# rapidshark-main-breakout-bottom-mk-1_0.net
KiCad netlist of a schematic drawn in EAGLE
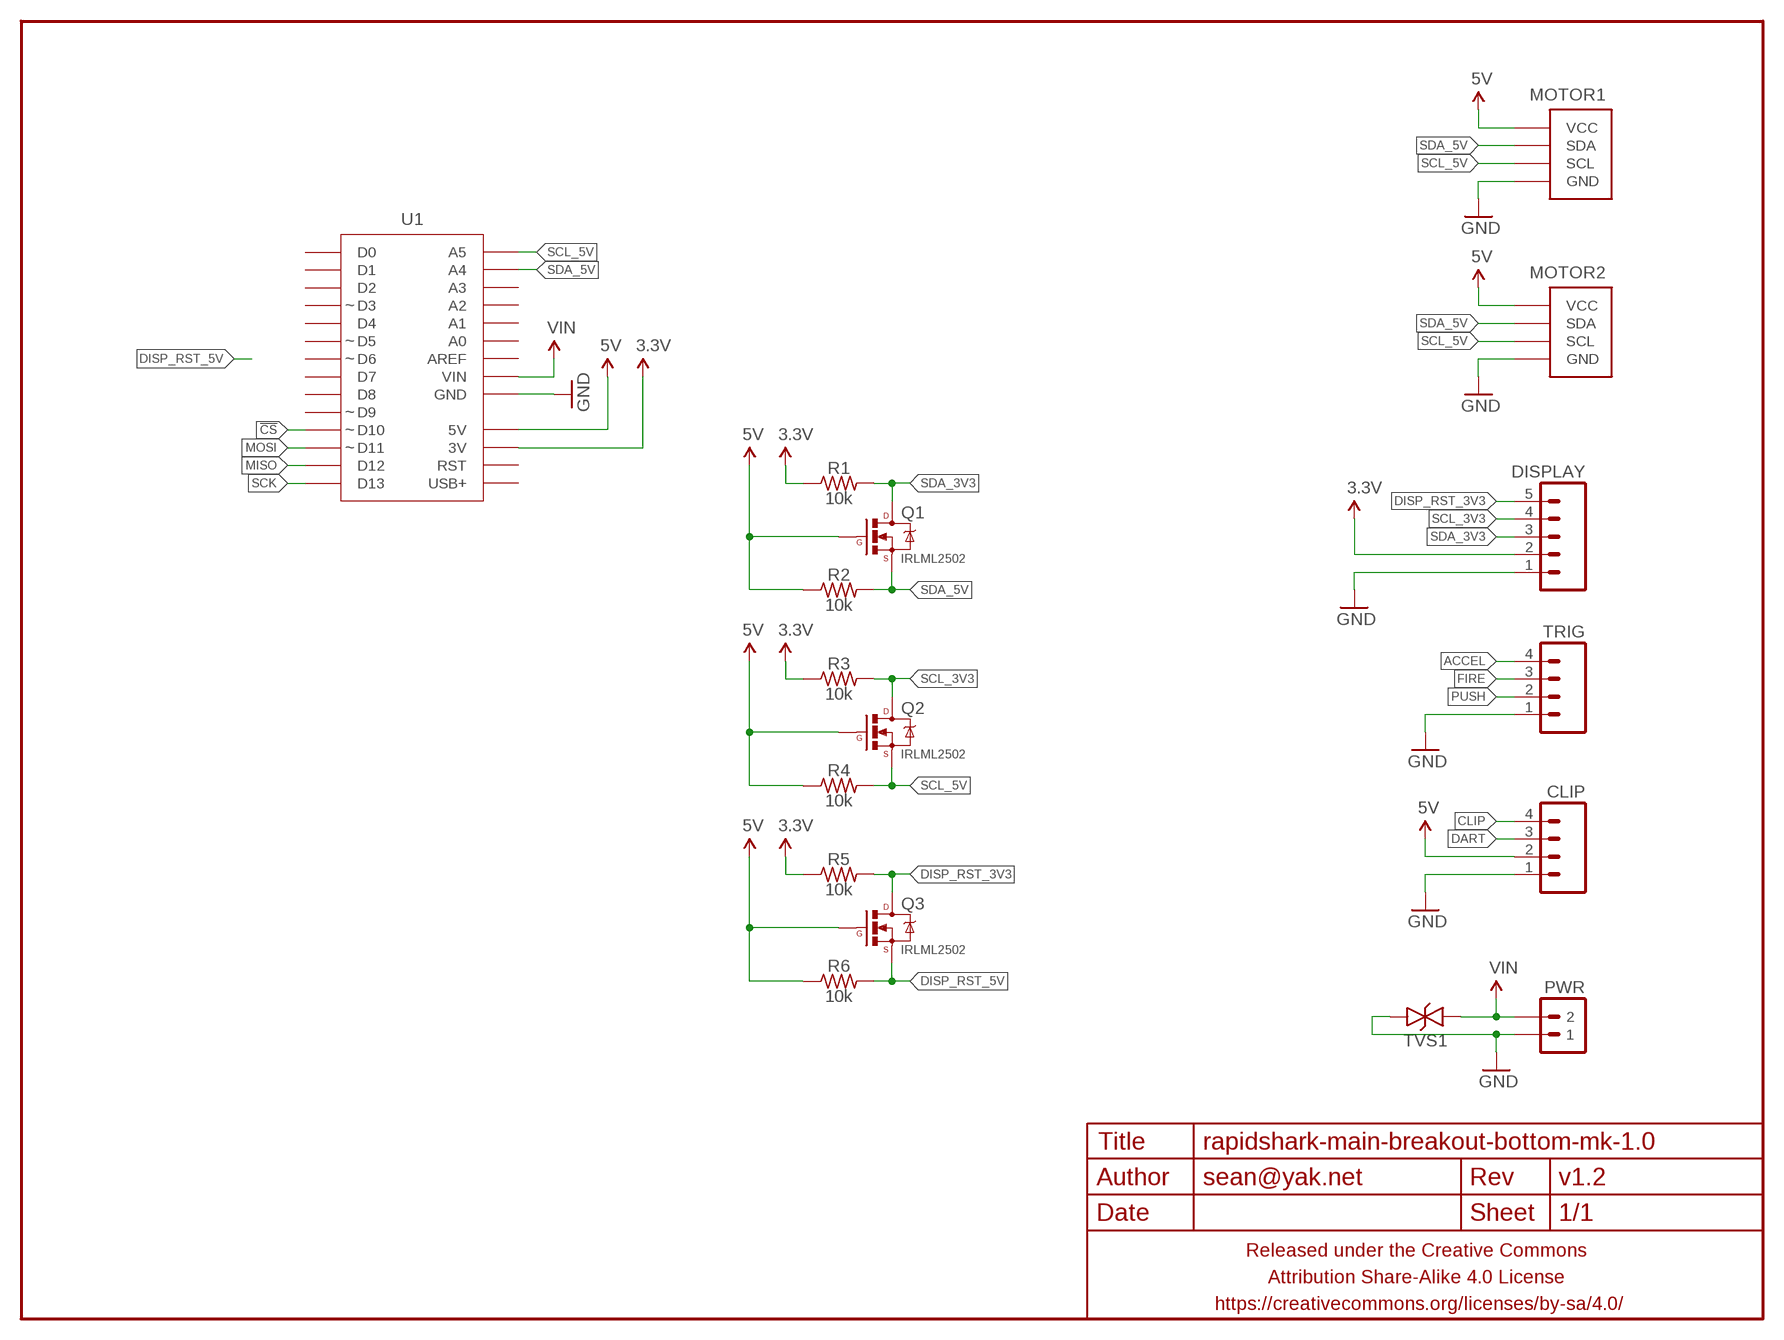
[diagram p0: schematic, sheet 1]

(export (version "E")
  (design (tool "Eeschema 10.0.6"))
  (components
    (comp (ref "CLIP")
      (value "M04JST-PTH-VERT")
      (footprint "eagle-import:JST-4-PH-VERT-PTH")
      (libsource (lib "eagle-import") (part "M04JST-PTH-VERT"))
    )
    (comp (ref "DISPLAY")
      (value "M05JST-PH-VERT-PTH")
      (footprint "eagle-import:JST-5-PH-VERT-PTH")
      (libsource (lib "eagle-import") (part "M05JST-PH-VERT-PTH"))
    )
    (comp (ref "FRAME1")
      (value "FRAME-LETTERNO_PACKAGE")
      (footprint "eagle-import:DUMMY")
      (fields (field (name "DESIGNER") "sean@yak.net") (field (name "VERSION") "v1.2"))
      (libsource (lib "eagle-import") (part "FRAME-LETTERNO_PACKAGE"))
    )
    (comp (ref "MOTOR1")
      (value "M04-I2CJST-4-PH-VERT-NS")
      (footprint "eagle-import:JST-4-PH-VERT-PTH")
      (libsource (lib "eagle-import") (part "M04-I2CJST-4-PH-VERT-NS"))
    )
    (comp (ref "MOTOR2")
      (value "M04-I2CJST-4-PH-VERT-NS")
      (footprint "eagle-import:JST-4-PH-VERT-PTH")
      (libsource (lib "eagle-import") (part "M04-I2CJST-4-PH-VERT-NS"))
    )
    (comp (ref "PWR")
      (value "M02PTH-CENTERED-R+")
      (footprint "eagle-import:1X02-CENTER-R+")
      (libsource (lib "eagle-import") (part "M02PTH-CENTERED-R+"))
    )
    (comp (ref "Q1")
      (value "IRLML2502")
      (footprint "eagle-import:SOT23")
      (libsource (lib "eagle-import") (part "MOSFET-NCHANNELIRLML2502"))
    )
    (comp (ref "Q2")
      (value "IRLML2502")
      (footprint "eagle-import:SOT23")
      (libsource (lib "eagle-import") (part "MOSFET-NCHANNELIRLML2502"))
    )
    (comp (ref "Q3")
      (value "IRLML2502")
      (footprint "eagle-import:SOT23")
      (libsource (lib "eagle-import") (part "MOSFET-NCHANNELIRLML2502"))
    )
    (comp (ref "R1")
      (value "10k")
      (footprint "eagle-import:R0603")
      (libsource (lib "eagle-import") (part "RESISTORR0603"))
    )
    (comp (ref "R2")
      (value "10k")
      (footprint "eagle-import:R0603")
      (libsource (lib "eagle-import") (part "RESISTORR0603"))
    )
    (comp (ref "R3")
      (value "10k")
      (footprint "eagle-import:R0603")
      (libsource (lib "eagle-import") (part "RESISTORR0603"))
    )
    (comp (ref "R4")
      (value "10k")
      (footprint "eagle-import:R0603")
      (libsource (lib "eagle-import") (part "RESISTORR0603"))
    )
    (comp (ref "R5")
      (value "10k")
      (footprint "eagle-import:R0603")
      (libsource (lib "eagle-import") (part "RESISTORR0603"))
    )
    (comp (ref "R6")
      (value "10k")
      (footprint "eagle-import:R0603")
      (libsource (lib "eagle-import") (part "RESISTORR0603"))
    )
    (comp (ref "TRIG")
      (value "M04JST-PTH-VERT")
      (footprint "eagle-import:JST-4-PH-VERT-PTH")
      (libsource (lib "eagle-import") (part "M04JST-PTH-VERT"))
    )
    (comp (ref "TVS1")
      (value "TVSSMA")
      (footprint "eagle-import:SMA-DIODE-TVS-BIDIR")
      (libsource (lib "eagle-import") (part "TVSSMA"))
    )
    (comp (ref "U1")
      (value "ADAFRUIT_METRO_MININOHOLES-OUTSIDER")
      (footprint "eagle-import:ADAFRUIT_METRO_MINI_OUTSIDER")
      (libsource (lib "eagle-import") (part "ADAFRUIT_METRO_MININOHOLES-OUTSIDER"))
    )
  )
  (nets
    (net (code "1") (name "/~{CS}") (class "Default")
      (node (ref "U1") (pin "11") (pinfunction "D10_11") (pintype "bidirectional"))
    )
    (net (code "2") (name "3.3V") (class "Default")
      (node (ref "DISPLAY") (pin "2") (pinfunction "2_2") (pintype "passive"))
      (node (ref "R1") (pin "1") (pinfunction "1_1") (pintype "passive"))
      (node (ref "R3") (pin "1") (pinfunction "1_1") (pintype "passive"))
      (node (ref "R5") (pin "1") (pinfunction "1_1") (pintype "passive"))
      (node (ref "U1") (pin "17") (pinfunction "3V_17") (pintype "bidirectional"))
    )
    (net (code "3") (name "5V") (class "Default")
      (node (ref "CLIP") (pin "2") (pinfunction "2_2") (pintype "passive"))
      (node (ref "MOTOR1") (pin "2") (pinfunction "VCC_2") (pintype "bidirectional"))
      (node (ref "MOTOR2") (pin "2") (pinfunction "VCC_2") (pintype "bidirectional"))
      (node (ref "Q1") (pin "1") (pinfunction "G_1") (pintype "passive"))
      (node (ref "Q2") (pin "1") (pinfunction "G_1") (pintype "passive"))
      (node (ref "Q3") (pin "1") (pinfunction "G_1") (pintype "passive"))
      (node (ref "R2") (pin "1") (pinfunction "1_1") (pintype "passive"))
      (node (ref "R4") (pin "1") (pinfunction "1_1") (pintype "passive"))
      (node (ref "R6") (pin "1") (pinfunction "1_1") (pintype "passive"))
      (node (ref "U1") (pin "18") (pinfunction "5V_18") (pintype "bidirectional"))
    )
    (net (code "4") (name "ACCEL") (class "Default")
      (node (ref "TRIG") (pin "4") (pinfunction "4_4") (pintype "passive"))
    )
    (net (code "5") (name "CLIP") (class "Default")
      (node (ref "CLIP") (pin "4") (pinfunction "4_4") (pintype "passive"))
    )
    (net (code "6") (name "DART") (class "Default")
      (node (ref "CLIP") (pin "3") (pinfunction "3_3") (pintype "passive"))
    )
    (net (code "7") (name "DISP_RST_3V3") (class "Default")
      (node (ref "DISPLAY") (pin "5") (pinfunction "5_5") (pintype "passive"))
      (node (ref "Q3") (pin "3") (pinfunction "D_3") (pintype "passive"))
      (node (ref "R5") (pin "2") (pinfunction "2_2") (pintype "passive"))
    )
    (net (code "8") (name "DISP_RST_5V") (class "Default")
      (node (ref "Q3") (pin "2") (pinfunction "S_2") (pintype "passive"))
      (node (ref "R6") (pin "2") (pinfunction "2_2") (pintype "passive"))
    )
    (net (code "9") (name "FIRE") (class "Default")
      (node (ref "TRIG") (pin "3") (pinfunction "3_3") (pintype "passive"))
    )
    (net (code "10") (name "GND") (class "Default")
      (node (ref "CLIP") (pin "1") (pinfunction "1_1") (pintype "passive"))
      (node (ref "DISPLAY") (pin "1") (pinfunction "1_1") (pintype "passive"))
      (node (ref "MOTOR1") (pin "1") (pinfunction "GND_1") (pintype "bidirectional"))
      (node (ref "MOTOR2") (pin "1") (pinfunction "GND_1") (pintype "bidirectional"))
      (node (ref "PWR") (pin "1") (pinfunction "1_1") (pintype "passive"))
      (node (ref "TRIG") (pin "1") (pinfunction "1_1") (pintype "passive"))
      (node (ref "TVS1") (pin "2") (pinfunction "2_2") (pintype "passive"))
      (node (ref "U1") (pin "19") (pinfunction "GND_19") (pintype "bidirectional"))
      (node (ref "U1") (pin "20") (pinfunction "GND_20") (pintype "bidirectional"))
    )
    (net (code "11") (name "MISO") (class "Default")
      (node (ref "U1") (pin "13") (pinfunction "D12_13") (pintype "bidirectional"))
    )
    (net (code "12") (name "MOSI") (class "Default")
      (node (ref "U1") (pin "12") (pinfunction "D11_12") (pintype "bidirectional"))
    )
    (net (code "13") (name "PUSH") (class "Default")
      (node (ref "TRIG") (pin "2") (pinfunction "2_2") (pintype "passive"))
    )
    (net (code "14") (name "SCK") (class "Default")
      (node (ref "U1") (pin "14") (pinfunction "D13_14") (pintype "bidirectional"))
    )
    (net (code "15") (name "SCL_3V3") (class "Default")
      (node (ref "DISPLAY") (pin "4") (pinfunction "4_4") (pintype "passive"))
      (node (ref "Q2") (pin "3") (pinfunction "D_3") (pintype "passive"))
      (node (ref "R3") (pin "2") (pinfunction "2_2") (pintype "passive"))
    )
    (net (code "16") (name "SCL_5V") (class "Default")
      (node (ref "MOTOR1") (pin "4") (pinfunction "SCL_4") (pintype "bidirectional"))
      (node (ref "MOTOR2") (pin "4") (pinfunction "SCL_4") (pintype "bidirectional"))
      (node (ref "Q2") (pin "2") (pinfunction "S_2") (pintype "passive"))
      (node (ref "R4") (pin "2") (pinfunction "2_2") (pintype "passive"))
      (node (ref "U1") (pin "28") (pinfunction "A5_28") (pintype "bidirectional"))
    )
    (net (code "17") (name "SDA_3V3") (class "Default")
      (node (ref "DISPLAY") (pin "3") (pinfunction "3_3") (pintype "passive"))
      (node (ref "Q1") (pin "3") (pinfunction "D_3") (pintype "passive"))
      (node (ref "R1") (pin "2") (pinfunction "2_2") (pintype "passive"))
    )
    (net (code "18") (name "SDA_5V") (class "Default")
      (node (ref "MOTOR1") (pin "3") (pinfunction "SDA_3") (pintype "bidirectional"))
      (node (ref "MOTOR2") (pin "3") (pinfunction "SDA_3") (pintype "bidirectional"))
      (node (ref "Q1") (pin "2") (pinfunction "S_2") (pintype "passive"))
      (node (ref "R2") (pin "2") (pinfunction "2_2") (pintype "passive"))
      (node (ref "U1") (pin "27") (pinfunction "A4_27") (pintype "bidirectional"))
    )
    (net (code "19") (name "VIN") (class "Default")
      (node (ref "PWR") (pin "2") (pinfunction "2_2") (pintype "passive"))
      (node (ref "TVS1") (pin "1") (pinfunction "1_1") (pintype "passive"))
      (node (ref "U1") (pin "21") (pinfunction "VIN_21") (pintype "bidirectional"))
    )
    (net (code "20") (name "unconnected-(U1-A0-Pad23)") (class "Default")
      (node (ref "U1") (pin "23") (pinfunction "A0_23") (pintype "bidirectional"))
    )
    (net (code "21") (name "unconnected-(U1-A1-Pad24)") (class "Default")
      (node (ref "U1") (pin "24") (pinfunction "A1_24") (pintype "bidirectional"))
    )
    (net (code "22") (name "unconnected-(U1-A2-Pad25)") (class "Default")
      (node (ref "U1") (pin "25") (pinfunction "A2_25") (pintype "bidirectional"))
    )
    (net (code "23") (name "unconnected-(U1-A3-Pad26)") (class "Default")
      (node (ref "U1") (pin "26") (pinfunction "A3_26") (pintype "bidirectional"))
    )
    (net (code "24") (name "unconnected-(U1-AREF-Pad22)") (class "Default")
      (node (ref "U1") (pin "22") (pinfunction "AREF_22") (pintype "bidirectional"))
    )
    (net (code "25") (name "unconnected-(U1-D0-Pad1)") (class "Default")
      (node (ref "U1") (pin "1") (pinfunction "D0_1") (pintype "bidirectional"))
    )
    (net (code "26") (name "unconnected-(U1-D1-Pad2)") (class "Default")
      (node (ref "U1") (pin "2") (pinfunction "D1_2") (pintype "bidirectional"))
    )
    (net (code "27") (name "unconnected-(U1-D2-Pad3)") (class "Default")
      (node (ref "U1") (pin "3") (pinfunction "D2_3") (pintype "bidirectional"))
    )
    (net (code "28") (name "unconnected-(U1-D3-Pad4)") (class "Default")
      (node (ref "U1") (pin "4") (pinfunction "D3_4") (pintype "bidirectional"))
    )
    (net (code "29") (name "unconnected-(U1-D4-Pad5)") (class "Default")
      (node (ref "U1") (pin "5") (pinfunction "D4_5") (pintype "bidirectional"))
    )
    (net (code "30") (name "unconnected-(U1-D5-Pad6)") (class "Default")
      (node (ref "U1") (pin "6") (pinfunction "D5_6") (pintype "bidirectional"))
    )
    (net (code "31") (name "unconnected-(U1-D6-Pad7)") (class "Default")
      (node (ref "U1") (pin "7") (pinfunction "D6_7") (pintype "bidirectional"))
    )
    (net (code "32") (name "unconnected-(U1-D7-Pad8)") (class "Default")
      (node (ref "U1") (pin "8") (pinfunction "D7_8") (pintype "bidirectional"))
    )
    (net (code "33") (name "unconnected-(U1-D8-Pad9)") (class "Default")
      (node (ref "U1") (pin "9") (pinfunction "D8_9") (pintype "bidirectional"))
    )
    (net (code "34") (name "unconnected-(U1-D9-Pad10)") (class "Default")
      (node (ref "U1") (pin "10") (pinfunction "D9_10") (pintype "bidirectional"))
    )
    (net (code "35") (name "unconnected-(U1-RST-Pad16)") (class "Default")
      (node (ref "U1") (pin "16") (pinfunction "RST_16") (pintype "bidirectional"))
    )
    (net (code "36") (name "unconnected-(U1-USB+-Pad15)") (class "Default")
      (node (ref "U1") (pin "15") (pinfunction "USB+_15") (pintype "bidirectional"))
    )
  )
)
